# Thunder_F722_Drone_Flight_Controller_202.net
KiCad netlist of a schematic drawn in EasyEDA Pro
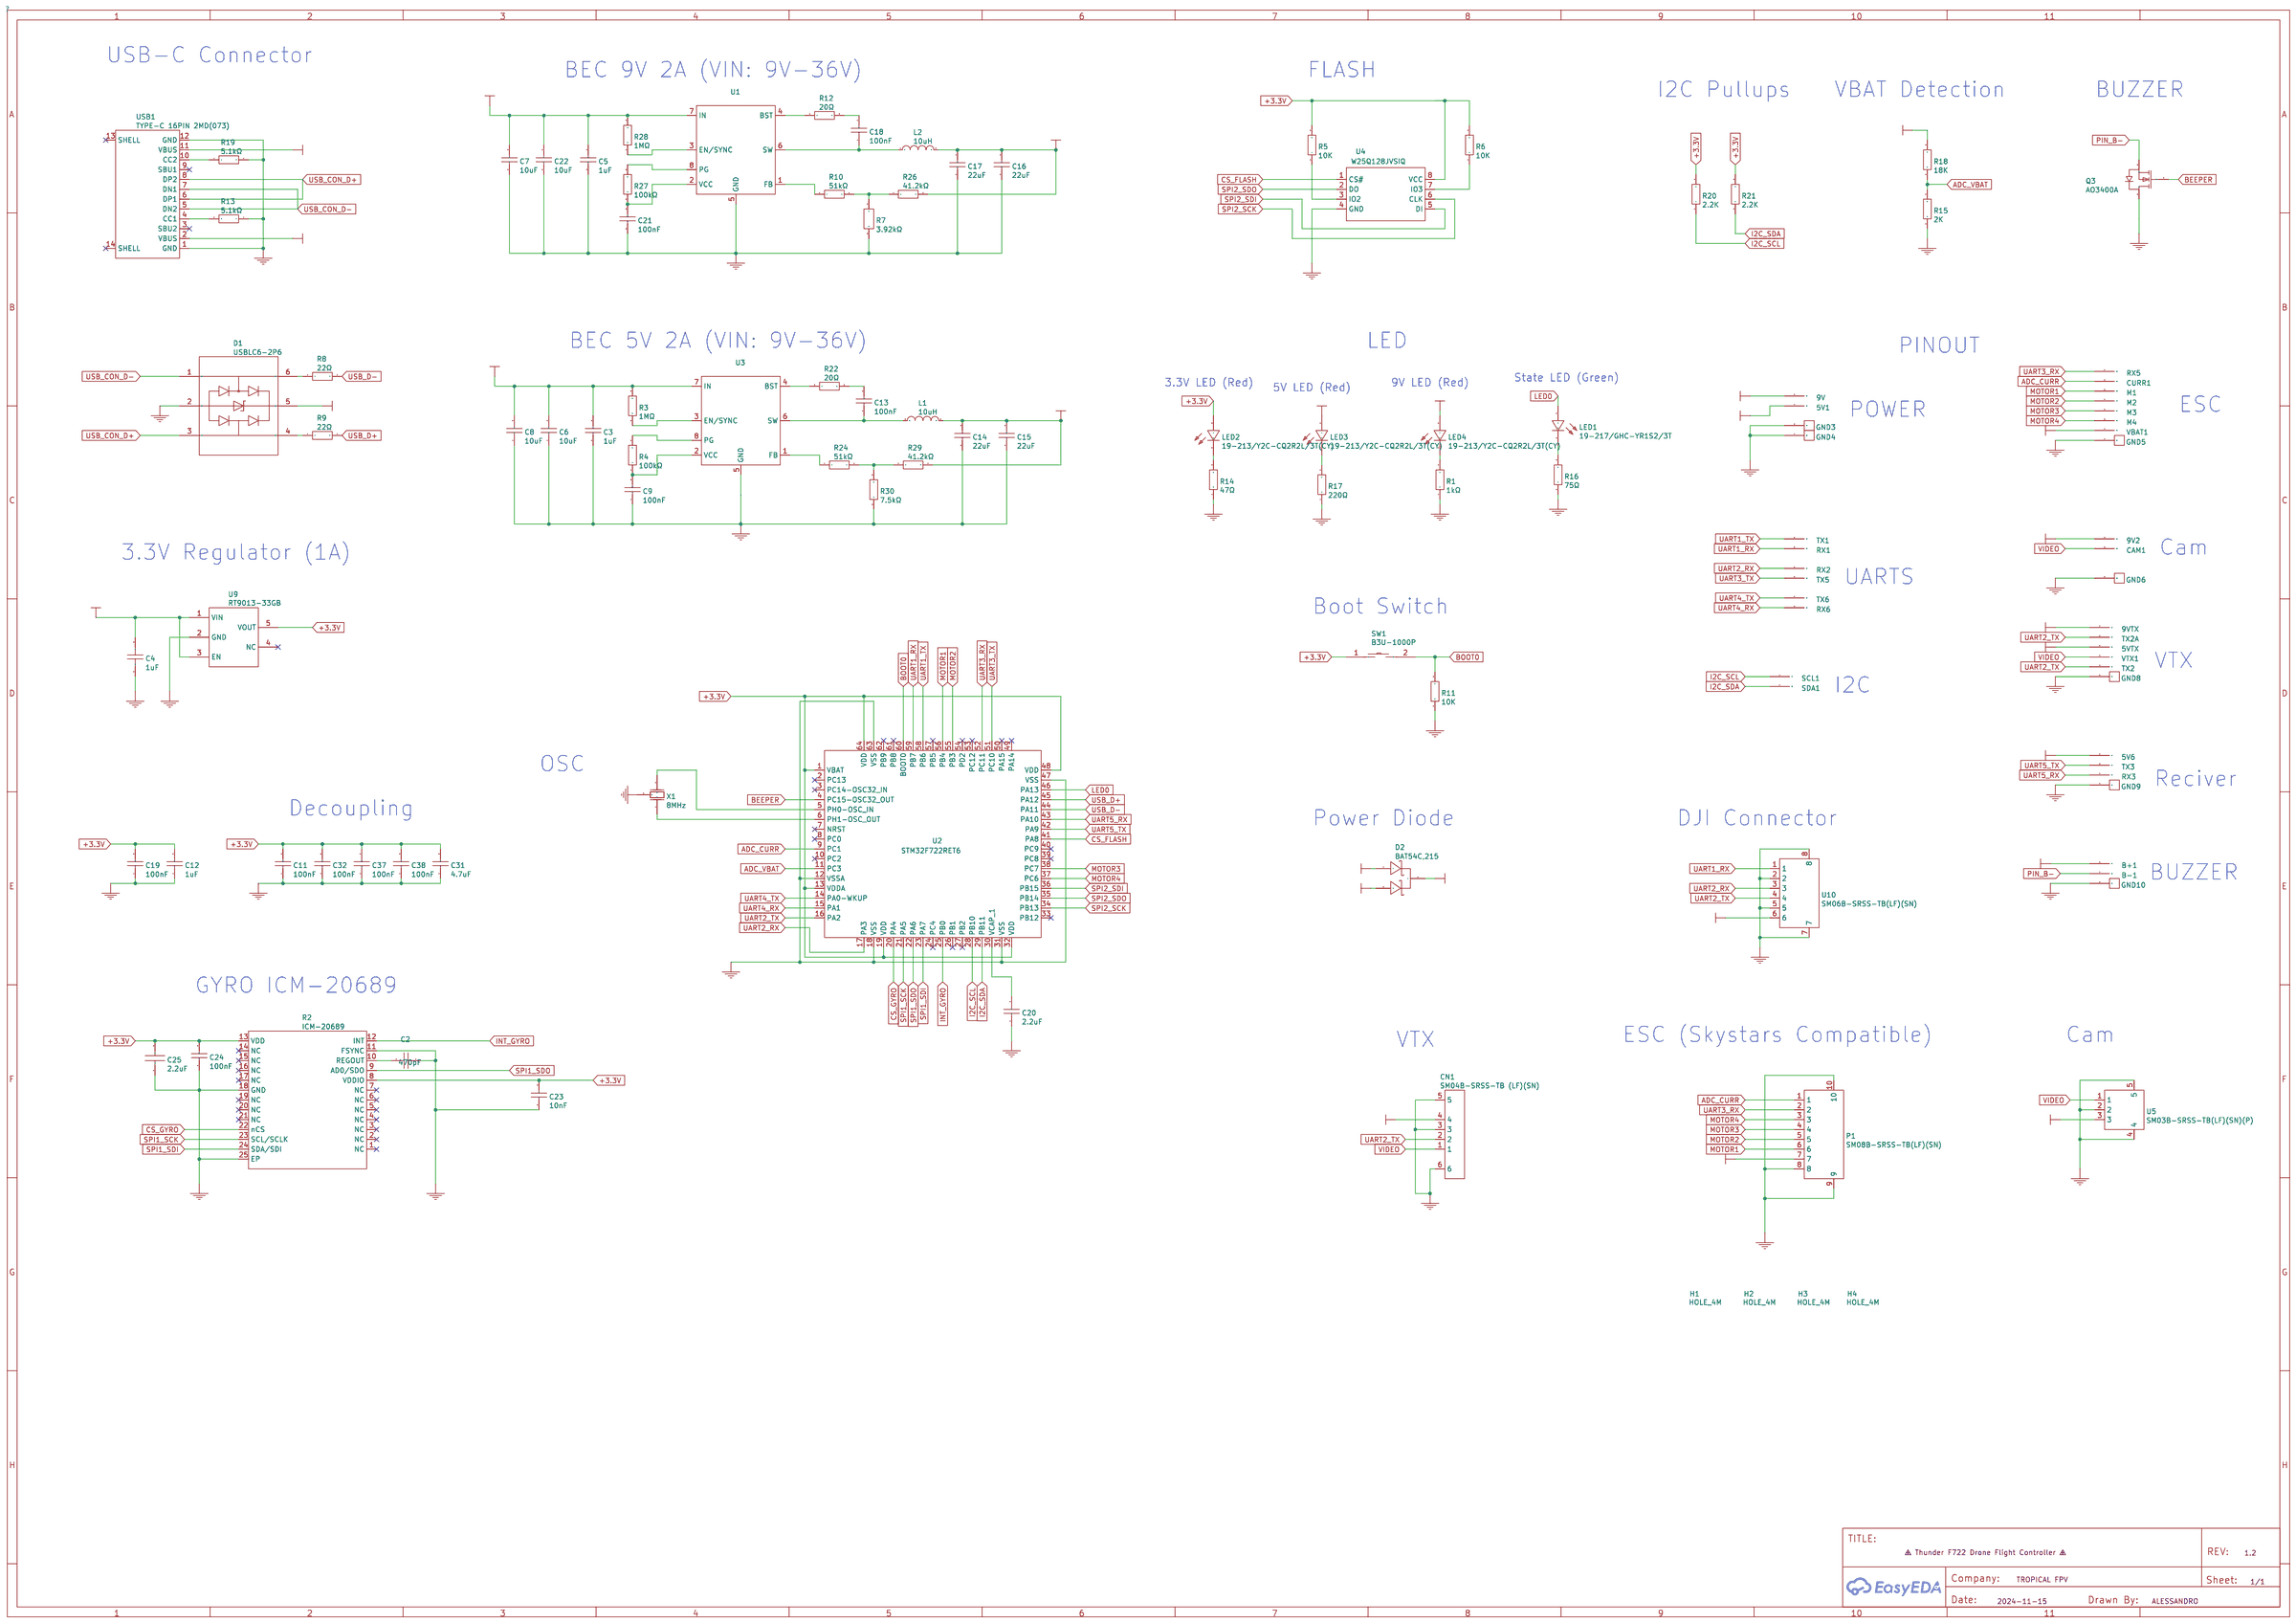
[diagram p0: schematic sheet]

(export (version "E")
  (design (tool "Eeschema 10.0.6"))
  (components
    (comp (ref "5V1")
      (value "ROUND SOLDER PADS WITH HOLE 1.5MM X 2.5MM COPY")
      (footprint "easyedapro:ROUND SOLDER PADS WITH HOLE 1MM X 1.75MM")
      (fields (field (name "Manufacturer Part") "solderpad"))
      (libsource (lib "easyedapro") (part "ROUND SOLDER PADS WITH HOLE 1.5MM X 2.5MM COPY"))
    )
    (comp (ref "5V6")
      (value "ROUND SOLDER PADS WITH HOLE 1.5MM X 2.5MM COPY")
      (footprint "easyedapro:ROUND SOLDER PADS WITH HOLE 1MM X 1.75MM")
      (fields (field (name "Manufacturer Part") "solderpad"))
      (libsource (lib "easyedapro") (part "ROUND SOLDER PADS WITH HOLE 1.5MM X 2.5MM COPY"))
    )
    (comp (ref "5VTX")
      (value "ROUND SOLDER PADS WITH HOLE 1.5MM X 2.5MM COPY")
      (footprint "easyedapro:ROUND SOLDER PADS WITH HOLE 1MM X 1.75MM")
      (fields (field (name "Manufacturer Part") "solderpad"))
      (libsource (lib "easyedapro") (part "ROUND SOLDER PADS WITH HOLE 1.5MM X 2.5MM COPY"))
    )
    (comp (ref "9V")
      (value "ROUND SOLDER PADS WITH HOLE 1.5MM X 2.5MM COPY")
      (footprint "easyedapro:ROUND SOLDER PADS WITH HOLE 1MM X 1.75MM")
      (fields (field (name "Manufacturer Part") "solderpad"))
      (libsource (lib "easyedapro") (part "ROUND SOLDER PADS WITH HOLE 1.5MM X 2.5MM COPY"))
    )
    (comp (ref "9V2")
      (value "ROUND SOLDER PADS WITH HOLE 1.5MM X 2.5MM COPY")
      (footprint "easyedapro:ROUND SOLDER PADS WITH HOLE 1MM X 1.75MM")
      (fields (field (name "Manufacturer Part") "solderpad"))
      (libsource (lib "easyedapro") (part "ROUND SOLDER PADS WITH HOLE 1.5MM X 2.5MM COPY"))
    )
    (comp (ref "9VTX")
      (value "ROUND SOLDER PADS WITH HOLE 1.5MM X 2.5MM COPY")
      (footprint "easyedapro:ROUND SOLDER PADS WITH HOLE 1MM X 1.75MM")
      (fields (field (name "Manufacturer Part") "solderpad"))
      (libsource (lib "easyedapro") (part "ROUND SOLDER PADS WITH HOLE 1.5MM X 2.5MM COPY"))
    )
    (comp (ref "B+1")
      (value "ROUND SOLDER PADS WITH HOLE 1.5MM X 2.5MM COPY")
      (footprint "easyedapro:ROUND SOLDER PADS WITH HOLE 1MM X 1.75MM")
      (fields (field (name "Manufacturer Part") "solderpad"))
      (libsource (lib "easyedapro") (part "ROUND SOLDER PADS WITH HOLE 1.5MM X 2.5MM COPY"))
    )
    (comp (ref "B-1")
      (value "ROUND SOLDER PADS WITH HOLE 1.5MM X 2.5MM COPY")
      (footprint "easyedapro:ROUND SOLDER PADS WITH HOLE 1MM X 1.75MM")
      (fields (field (name "Manufacturer Part") "solderpad"))
      (libsource (lib "easyedapro") (part "ROUND SOLDER PADS WITH HOLE 1.5MM X 2.5MM COPY"))
    )
    (comp (ref "C2")
      (value "470pF")
      (footprint "easyedapro:C0402")
      (fields (field (name "Manufacturer Part") "0402B471K500NT") (field (name "Manufacturer") "FH(风华)"))
      (libsource (lib "easyedapro") (part "470pF"))
    )
    (comp (ref "C3")
      (value "1uF")
      (footprint "easyedapro:C0603")
      (fields (field (name "Manufacturer Part") "CL10A105KB8NNNC") (field (name "Manufacturer") "SAMSUNG"))
      (libsource (lib "easyedapro") (part "1uF"))
    )
    (comp (ref "C4")
      (value "1uF")
      (footprint "easyedapro:C0402")
      (fields (field (name "Manufacturer Part") "CL05A105KA5NQNC") (field (name "Manufacturer") "SAMSUNG"))
      (libsource (lib "") (part "1uF_1"))
    )
    (comp (ref "C5")
      (value "1uF")
      (footprint "easyedapro:C0603")
      (fields (field (name "Manufacturer Part") "CL10A105KB8NNNC") (field (name "Manufacturer") "SAMSUNG"))
      (libsource (lib "easyedapro") (part "1uF"))
    )
    (comp (ref "C6")
      (value "10uF")
      (footprint "easyedapro:C1206")
      (fields (field (name "Manufacturer Part") "CL31A106KBHNNNE") (field (name "Manufacturer") "SAMSUNG"))
      (libsource (lib "easyedapro") (part "10uF"))
    )
    (comp (ref "C7")
      (value "10uF")
      (footprint "easyedapro:C1206")
      (fields (field (name "Manufacturer Part") "CL31A106KBHNNNE") (field (name "Manufacturer") "SAMSUNG"))
      (libsource (lib "easyedapro") (part "10uF"))
    )
    (comp (ref "C8")
      (value "10uF")
      (footprint "easyedapro:C1206")
      (fields (field (name "Manufacturer Part") "CL31A106KBHNNNE") (field (name "Manufacturer") "SAMSUNG"))
      (libsource (lib "easyedapro") (part "10uF"))
    )
    (comp (ref "C9")
      (value "100nF")
      (footprint "easyedapro:C0402")
      (fields (field (name "Manufacturer Part") "CL05B104KO5NNNC") (field (name "Manufacturer") "SAMSUNG"))
      (libsource (lib "easyedapro") (part "100nF"))
    )
    (comp (ref "C11")
      (value "100nF")
      (footprint "easyedapro:C0402")
      (fields (field (name "Manufacturer Part") "CL05B104KO5NNNC") (field (name "Manufacturer") "SAMSUNG"))
      (libsource (lib "easyedapro") (part "100nF"))
    )
    (comp (ref "C12")
      (value "1uF")
      (footprint "easyedapro:C0603")
      (fields (field (name "Manufacturer Part") "CL10A105KB8NNNC") (field (name "Manufacturer") "SAMSUNG"))
      (libsource (lib "easyedapro") (part "1uF"))
    )
    (comp (ref "C13")
      (value "100nF")
      (footprint "easyedapro:C0402")
      (fields (field (name "Manufacturer Part") "CL05B104KO5NNNC") (field (name "Manufacturer") "SAMSUNG"))
      (libsource (lib "easyedapro") (part "100nF"))
    )
    (comp (ref "C14")
      (value "22uF")
      (footprint "easyedapro:C1206")
      (fields
        (field (name "Manufacturer Part") "CL31A226KPHNNNE")
        (field (name "Manufacturer") "SAMSUNG(三星)")
      )
      (libsource (lib "easyedapro") (part "22uF"))
    )
    (comp (ref "C15")
      (value "22uF")
      (footprint "easyedapro:C1206")
      (fields
        (field (name "Manufacturer Part") "CL31A226KPHNNNE")
        (field (name "Manufacturer") "SAMSUNG(三星)")
      )
      (libsource (lib "easyedapro") (part "22uF"))
    )
    (comp (ref "C16")
      (value "22uF")
      (footprint "easyedapro:C1206")
      (fields
        (field (name "Manufacturer Part") "CL31A226KPHNNNE")
        (field (name "Manufacturer") "SAMSUNG(三星)")
      )
      (libsource (lib "easyedapro") (part "22uF"))
    )
    (comp (ref "C17")
      (value "22uF")
      (footprint "easyedapro:C1206")
      (fields
        (field (name "Manufacturer Part") "CL31A226KPHNNNE")
        (field (name "Manufacturer") "SAMSUNG(三星)")
      )
      (libsource (lib "easyedapro") (part "22uF"))
    )
    (comp (ref "C18")
      (value "100nF")
      (footprint "easyedapro:C0402")
      (fields (field (name "Manufacturer Part") "CL05B104KO5NNNC") (field (name "Manufacturer") "SAMSUNG"))
      (libsource (lib "easyedapro") (part "100nF"))
    )
    (comp (ref "C19")
      (value "100nF")
      (footprint "easyedapro:C0402")
      (fields (field (name "Manufacturer Part") "CL05B104KO5NNNC") (field (name "Manufacturer") "SAMSUNG"))
      (libsource (lib "easyedapro") (part "100nF"))
    )
    (comp (ref "C20")
      (value "2.2uF")
      (footprint "easyedapro:C0603")
      (fields (field (name "Manufacturer Part") "CL10A225KO8NNNC") (field (name "Manufacturer") "SAMSUNG"))
      (libsource (lib "") (part "2.2uF_1"))
    )
    (comp (ref "C21")
      (value "100nF")
      (footprint "easyedapro:C0402")
      (fields (field (name "Manufacturer Part") "CL05B104KO5NNNC") (field (name "Manufacturer") "SAMSUNG"))
      (libsource (lib "easyedapro") (part "100nF"))
    )
    (comp (ref "C22")
      (value "10uF")
      (footprint "easyedapro:C1206")
      (fields (field (name "Manufacturer Part") "CL31A106KBHNNNE") (field (name "Manufacturer") "SAMSUNG"))
      (libsource (lib "easyedapro") (part "10uF"))
    )
    (comp (ref "C23")
      (value "10nF")
      (footprint "easyedapro:C0402")
      (fields
        (field (name "Manufacturer Part") "CL05B103KB5NNNC")
        (field (name "Manufacturer") "SAMSUNG(三星)")
      )
      (libsource (lib "easyedapro") (part "10nF"))
    )
    (comp (ref "C24")
      (value "100nF")
      (footprint "easyedapro:C0402")
      (fields (field (name "Manufacturer Part") "CL05B104KO5NNNC") (field (name "Manufacturer") "SAMSUNG"))
      (libsource (lib "easyedapro") (part "100nF"))
    )
    (comp (ref "C25")
      (value "2.2uF")
      (footprint "easyedapro:C0402")
      (fields
        (field (name "Manufacturer Part") "CL05A225MQ5NSNC")
        (field (name "Manufacturer") "SAMSUNG(三星)")
      )
      (libsource (lib "easyedapro") (part "2.2uF"))
    )
    (comp (ref "C31")
      (value "4.7uF")
      (footprint "easyedapro:C0603")
      (fields (field (name "Manufacturer Part") "CL10A475KO8NNNC") (field (name "Manufacturer") "SAMSUNG"))
      (libsource (lib "easyedapro") (part "4.7uF"))
    )
    (comp (ref "C32")
      (value "100nF")
      (footprint "easyedapro:C0402")
      (fields (field (name "Manufacturer Part") "CL05B104KO5NNNC") (field (name "Manufacturer") "SAMSUNG"))
      (libsource (lib "easyedapro") (part "100nF"))
    )
    (comp (ref "C37")
      (value "100nF")
      (footprint "easyedapro:C0402")
      (fields (field (name "Manufacturer Part") "CL05B104KO5NNNC") (field (name "Manufacturer") "SAMSUNG"))
      (libsource (lib "easyedapro") (part "100nF"))
    )
    (comp (ref "C38")
      (value "100nF")
      (footprint "easyedapro:C0402")
      (fields (field (name "Manufacturer Part") "CL05B104KO5NNNC") (field (name "Manufacturer") "SAMSUNG"))
      (libsource (lib "easyedapro") (part "100nF"))
    )
    (comp (ref "CAM1")
      (value "ROUND SOLDER PADS WITH HOLE 1.5MM X 2.5MM COPY")
      (footprint "easyedapro:ROUND SOLDER PADS WITH HOLE 1MM X 1.75MM")
      (fields (field (name "Manufacturer Part") "solderpad"))
      (libsource (lib "easyedapro") (part "ROUND SOLDER PADS WITH HOLE 1.5MM X 2.5MM COPY"))
    )
    (comp (ref "CN1")
      (value "SM04B-SRSS-TB (LF)(SN)")
      (footprint "easyedapro:CONN-SMD_4P-P1.00_SM04B-SRSS-TB-LF-SN")
      (fields (field (name "Manufacturer Part") "SM04B-SRSS-TB(LF)(SN)") (field (name "Manufacturer") "JST"))
      (libsource (lib "easyedapro") (part "SM04B-SRSS-TB (LF)(SN)"))
    )
    (comp (ref "CURR1")
      (value "ROUND SOLDER PADS WITH HOLE 1.5MM X 2.5MM COPY")
      (footprint "easyedapro:ROUND SOLDER PADS WITH HOLE 1MM X 1.75MM")
      (fields (field (name "Manufacturer Part") "solderpad"))
      (libsource (lib "easyedapro") (part "ROUND SOLDER PADS WITH HOLE 1.5MM X 2.5MM COPY"))
    )
    (comp (ref "D1")
      (value "USBLC6-2P6")
      (footprint "easyedapro:SOT-666-6_L1.6-W1.2-P0.50-LS1.6-BR")
      (fields (field (name "Manufacturer") "STMicroelectronics"))
      (libsource (lib "easyedapro") (part "USBLC6-2P6"))
    )
    (comp (ref "D2")
      (value "BAT54C,215")
      (footprint "easyedapro:SOT-23-3_L2.9-W1.6-P1.90-LS2.8-BR")
      (fields (field (name "Manufacturer") "Nexperia(安世)"))
      (libsource (lib "easyedapro") (part "BAT54C,215"))
    )
    (comp (ref "GND3")
      (value "RECTANGLE SOLDER PADS WITH HOLE 1.5MM X 2.5MM")
      (footprint "easyedapro:RECTANGLE SOLDER PADS WITH HOLE 1.25MM X 1.75MM")
      (fields (field (name "Manufacturer Part") "solderpad"))
      (libsource (lib "easyedapro") (part "RECTANGLE SOLDER PADS WITH HOLE 1.5MM X 2.5MM"))
    )
    (comp (ref "GND4")
      (value "RECTANGLE SOLDER PADS WITH HOLE 1.5MM X 2.5MM")
      (footprint "easyedapro:RECTANGLE SOLDER PADS WITH HOLE 1.25MM X 1.75MM")
      (fields (field (name "Manufacturer Part") "solderpad"))
      (libsource (lib "easyedapro") (part "RECTANGLE SOLDER PADS WITH HOLE 1.5MM X 2.5MM"))
    )
    (comp (ref "GND5")
      (value "RECTANGLE SOLDER PADS WITH HOLE 1.5MM X 2.5MM")
      (footprint "easyedapro:RECTANGLE SOLDER PADS WITH HOLE 1.25MM X 1.75MM")
      (fields (field (name "Manufacturer Part") "solderpad"))
      (libsource (lib "easyedapro") (part "RECTANGLE SOLDER PADS WITH HOLE 1.5MM X 2.5MM"))
    )
    (comp (ref "GND6")
      (value "RECTANGLE SOLDER PADS WITH HOLE 1.5MM X 2.5MM")
      (footprint "easyedapro:RECTANGLE SOLDER PADS WITH HOLE 1.25MM X 1.75MM")
      (fields (field (name "Manufacturer Part") "solderpad"))
      (libsource (lib "easyedapro") (part "RECTANGLE SOLDER PADS WITH HOLE 1.5MM X 2.5MM"))
    )
    (comp (ref "GND8")
      (value "RECTANGLE SOLDER PADS WITH HOLE 1.5MM X 2.5MM")
      (footprint "easyedapro:RECTANGLE SOLDER PADS WITH HOLE 1.25MM X 1.75MM")
      (fields (field (name "Manufacturer Part") "solderpad"))
      (libsource (lib "easyedapro") (part "RECTANGLE SOLDER PADS WITH HOLE 1.5MM X 2.5MM"))
    )
    (comp (ref "GND9")
      (value "RECTANGLE SOLDER PADS WITH HOLE 1.5MM X 2.5MM")
      (footprint "easyedapro:RECTANGLE SOLDER PADS WITH HOLE 1.25MM X 1.75MM")
      (fields (field (name "Manufacturer Part") "solderpad"))
      (libsource (lib "easyedapro") (part "RECTANGLE SOLDER PADS WITH HOLE 1.5MM X 2.5MM"))
    )
    (comp (ref "GND10")
      (value "RECTANGLE SOLDER PADS WITH HOLE 1.5MM X 2.5MM")
      (footprint "easyedapro:RECTANGLE SOLDER PADS WITH HOLE 1.25MM X 1.75MM")
      (fields (field (name "Manufacturer Part") "solderpad"))
      (libsource (lib "easyedapro") (part "RECTANGLE SOLDER PADS WITH HOLE 1.5MM X 2.5MM"))
    )
    (comp (ref "H1")
      (value "HOLE_4M")
      (footprint "easyedapro:HOLE_4MM")
      (libsource (lib "easyedapro") (part "HOLE_4M"))
    )
    (comp (ref "H2")
      (value "HOLE_4M")
      (footprint "easyedapro:HOLE_4MM")
      (libsource (lib "easyedapro") (part "HOLE_4M"))
    )
    (comp (ref "H3")
      (value "HOLE_4M")
      (footprint "easyedapro:HOLE_4MM")
      (libsource (lib "easyedapro") (part "HOLE_4M"))
    )
    (comp (ref "H4")
      (value "HOLE_4M")
      (footprint "easyedapro:HOLE_4MM")
      (libsource (lib "easyedapro") (part "HOLE_4M"))
    )
    (comp (ref "L1")
      (value "10uH")
      (footprint "easyedapro:IND-SMD_L4.4-W4.2_PSPMAA0412")
      (fields (field (name "Manufacturer Part") "YSPI0420-100M") (field (name "Manufacturer") "YJYCOIN(益嘉源)"))
      (libsource (lib "easyedapro") (part "10uH"))
    )
    (comp (ref "L2")
      (value "10uH")
      (footprint "easyedapro:IND-SMD_L4.4-W4.2_PSPMAA0412")
      (fields (field (name "Manufacturer Part") "YSPI0420-100M") (field (name "Manufacturer") "YJYCOIN(益嘉源)"))
      (libsource (lib "easyedapro") (part "10uH"))
    )
    (comp (ref "LED1")
      (value "19-217/GHC-YR1S2/3T")
      (footprint "easyedapro:LED0603-R-RD")
      (fields (field (name "Manufacturer") "EVERLIGHT"))
      (libsource (lib "easyedapro") (part "19-217/GHC-YR1S2/3T"))
    )
    (comp (ref "LED2")
      (value "19-213/Y2C-CQ2R2L/3T(CY)")
      (footprint "easyedapro:LED0603-RD-YELLOW")
      (fields (field (name "Manufacturer") "EVERLIGHT(亿光)"))
      (libsource (lib "easyedapro") (part "19-213/Y2C-CQ2R2L/3T(CY)"))
    )
    (comp (ref "LED3")
      (value "19-213/Y2C-CQ2R2L/3T(CY)")
      (footprint "easyedapro:LED0603-RD-YELLOW")
      (fields (field (name "Manufacturer") "EVERLIGHT(亿光)"))
      (libsource (lib "easyedapro") (part "19-213/Y2C-CQ2R2L/3T(CY)"))
    )
    (comp (ref "LED4")
      (value "19-213/Y2C-CQ2R2L/3T(CY)")
      (footprint "easyedapro:LED0603-RD-YELLOW")
      (fields (field (name "Manufacturer") "EVERLIGHT(亿光)"))
      (libsource (lib "easyedapro") (part "19-213/Y2C-CQ2R2L/3T(CY)"))
    )
    (comp (ref "M1")
      (value "ROUND SOLDER PADS WITH HOLE 1.5MM X 2.5MM COPY")
      (footprint "easyedapro:ROUND SOLDER PADS WITH HOLE 1MM X 1.75MM")
      (fields (field (name "Manufacturer Part") "solderpad"))
      (libsource (lib "easyedapro") (part "ROUND SOLDER PADS WITH HOLE 1.5MM X 2.5MM COPY"))
    )
    (comp (ref "M2")
      (value "ROUND SOLDER PADS WITH HOLE 1.5MM X 2.5MM COPY")
      (footprint "easyedapro:ROUND SOLDER PADS WITH HOLE 1MM X 1.75MM")
      (fields (field (name "Manufacturer Part") "solderpad"))
      (libsource (lib "easyedapro") (part "ROUND SOLDER PADS WITH HOLE 1.5MM X 2.5MM COPY"))
    )
    (comp (ref "M3")
      (value "ROUND SOLDER PADS WITH HOLE 1.5MM X 2.5MM COPY")
      (footprint "easyedapro:ROUND SOLDER PADS WITH HOLE 1MM X 1.75MM")
      (fields (field (name "Manufacturer Part") "solderpad"))
      (libsource (lib "easyedapro") (part "ROUND SOLDER PADS WITH HOLE 1.5MM X 2.5MM COPY"))
    )
    (comp (ref "M4")
      (value "ROUND SOLDER PADS WITH HOLE 1.5MM X 2.5MM COPY")
      (footprint "easyedapro:ROUND SOLDER PADS WITH HOLE 1MM X 1.75MM")
      (fields (field (name "Manufacturer Part") "solderpad"))
      (libsource (lib "easyedapro") (part "ROUND SOLDER PADS WITH HOLE 1.5MM X 2.5MM COPY"))
    )
    (comp (ref "P1")
      (value "SM08B-SRSS-TB(LF)(SN)")
      (footprint "easyedapro:CONN-TH_SM08B-SRSS-TB-LF-SN")
      (fields (field (name "Manufacturer") "JST"))
      (libsource (lib "easyedapro") (part "SM08B-SRSS-TB(LF)(SN)"))
    )
    (comp (ref "Q3")
      (value "AO3400A")
      (footprint "easyedapro:SOT-23-3_L2.9-W1.6-P1.90-LS2.8-BR")
      (fields (field (name "Manufacturer") "AOS"))
      (libsource (lib "easyedapro") (part "AO3400A"))
    )
    (comp (ref "R1")
      (value "1kΩ")
      (footprint "easyedapro:R0603")
      (fields
        (field (name "Manufacturer Part") "0603WAF1001T5E")
        (field (name "Manufacturer") "UNI-ROYAL(厚声)")
      )
      (libsource (lib "easyedapro") (part "1kΩ"))
    )
    (comp (ref "R2")
      (value "ICM-20689")
      (footprint "easyedapro:QFN-24_L4.0-W4.0-P0.50-TL-EP2.6")
      (fields (field (name "Manufacturer") "TDK InvenSense(应美盛)"))
      (libsource (lib "easyedapro") (part "ICM-20689"))
    )
    (comp (ref "R3")
      (value "1MΩ")
      (footprint "easyedapro:R0603")
      (fields
        (field (name "Manufacturer Part") "0603WAF1004T5E")
        (field (name "Manufacturer") "UNI-ROYAL(厚声)")
      )
      (libsource (lib "easyedapro") (part "1MΩ"))
    )
    (comp (ref "R4")
      (value "100kΩ")
      (footprint "easyedapro:R0402")
      (fields
        (field (name "Manufacturer Part") "0402WGF1003TCE")
        (field (name "Manufacturer") "UNI-ROYAL(厚声)")
      )
      (libsource (lib "easyedapro") (part "100kΩ"))
    )
    (comp (ref "R5")
      (value "10K")
      (footprint "easyedapro:R0402")
      (fields (field (name "Manufacturer Part") "0402WGF1002TCE") (field (name "Manufacturer") "UniOhm"))
      (libsource (lib "easyedapro") (part "10K"))
    )
    (comp (ref "R6")
      (value "10K")
      (footprint "easyedapro:R0402")
      (fields (field (name "Manufacturer Part") "0402WGF1002TCE") (field (name "Manufacturer") "UniOhm"))
      (libsource (lib "easyedapro") (part "10K"))
    )
    (comp (ref "R7")
      (value "3.92kΩ")
      (footprint "easyedapro:R1206")
      (fields
        (field (name "Manufacturer Part") "1206W4F3921T5E")
        (field (name "Manufacturer") "UNI-ROYAL(厚声)")
      )
      (libsource (lib "easyedapro") (part "3.92kΩ"))
    )
    (comp (ref "R8")
      (value "22Ω")
      (footprint "easyedapro:R0402")
      (fields
        (field (name "Manufacturer Part") "0402WGF220JTCE")
        (field (name "Manufacturer") "UNI-ROYAL(厚声)")
      )
      (libsource (lib "easyedapro") (part "22Ω"))
    )
    (comp (ref "R9")
      (value "22Ω")
      (footprint "easyedapro:R0402")
      (fields
        (field (name "Manufacturer Part") "0402WGF220JTCE")
        (field (name "Manufacturer") "UNI-ROYAL(厚声)")
      )
      (libsource (lib "easyedapro") (part "22Ω"))
    )
    (comp (ref "R10")
      (value "51kΩ")
      (footprint "easyedapro:R0402")
      (fields
        (field (name "Manufacturer Part") "0402WGF5102TCE")
        (field (name "Manufacturer") "UNI-ROYAL(厚声)")
      )
      (libsource (lib "easyedapro") (part "51kΩ"))
    )
    (comp (ref "R11")
      (value "10K")
      (footprint "easyedapro:R0402")
      (fields (field (name "Manufacturer Part") "0402WGF1002TCE") (field (name "Manufacturer") "UniOhm"))
      (libsource (lib "easyedapro") (part "10K"))
    )
    (comp (ref "R12")
      (value "20Ω")
      (footprint "easyedapro:R0603")
      (fields
        (field (name "Manufacturer Part") "0603WAF200JT5E")
        (field (name "Manufacturer") "UNI-ROYAL(厚声)")
      )
      (libsource (lib "easyedapro") (part "20Ω"))
    )
    (comp (ref "R13")
      (value "5.1kΩ")
      (footprint "easyedapro:R0402")
      (fields
        (field (name "Manufacturer Part") "0402WGF5101TCE")
        (field (name "Manufacturer") "UNI-ROYAL(厚声)")
      )
      (libsource (lib "easyedapro") (part "5.1kΩ"))
    )
    (comp (ref "R14")
      (value "47Ω")
      (footprint "easyedapro:R0402")
      (fields (field (name "Manufacturer Part") "0402WGF470JTCE") (field (name "Manufacturer") "UniOhm"))
      (libsource (lib "easyedapro") (part "47Ω"))
    )
    (comp (ref "R15")
      (value "2K")
      (footprint "easyedapro:R0402")
      (fields (field (name "Manufacturer Part") "0402WGF2001TCE") (field (name "Manufacturer") "UniOhm"))
      (libsource (lib "easyedapro") (part "2K"))
    )
    (comp (ref "R16")
      (value "75Ω")
      (footprint "easyedapro:R0603")
      (fields (field (name "Manufacturer Part") "0603WAF750JT5E") (field (name "Manufacturer") "UniOhm"))
      (libsource (lib "easyedapro") (part "75Ω"))
    )
    (comp (ref "R17")
      (value "220Ω")
      (footprint "easyedapro:R0402")
      (fields (field (name "Manufacturer Part") "0402WGF2200TCE") (field (name "Manufacturer") "UniOhm"))
      (libsource (lib "easyedapro") (part "220Ω"))
    )
    (comp (ref "R18")
      (value "18K")
      (footprint "easyedapro:R0402")
      (fields (field (name "Manufacturer Part") "0402WGF1802TCE") (field (name "Manufacturer") "UniOhm"))
      (libsource (lib "easyedapro") (part "18K"))
    )
    (comp (ref "R19")
      (value "5.1kΩ")
      (footprint "easyedapro:R0402")
      (fields
        (field (name "Manufacturer Part") "0402WGF5101TCE")
        (field (name "Manufacturer") "UNI-ROYAL(厚声)")
      )
      (libsource (lib "easyedapro") (part "5.1kΩ"))
    )
    (comp (ref "R20")
      (value "2.2K")
      (footprint "easyedapro:R0402")
      (fields (field (name "Manufacturer Part") "0402WGF2201TCE") (field (name "Manufacturer") "UniOhm"))
      (libsource (lib "easyedapro") (part "2.2K"))
    )
    (comp (ref "R21")
      (value "2.2K")
      (footprint "easyedapro:R0402")
      (fields (field (name "Manufacturer Part") "0402WGF2201TCE") (field (name "Manufacturer") "UniOhm"))
      (libsource (lib "easyedapro") (part "2.2K"))
    )
    (comp (ref "R22")
      (value "20Ω")
      (footprint "easyedapro:R0603")
      (fields
        (field (name "Manufacturer Part") "0603WAF200JT5E")
        (field (name "Manufacturer") "UNI-ROYAL(厚声)")
      )
      (libsource (lib "easyedapro") (part "20Ω"))
    )
    (comp (ref "R24")
      (value "51kΩ")
      (footprint "easyedapro:R0402")
      (fields
        (field (name "Manufacturer Part") "0402WGF5102TCE")
        (field (name "Manufacturer") "UNI-ROYAL(厚声)")
      )
      (libsource (lib "easyedapro") (part "51kΩ"))
    )
    (comp (ref "R26")
      (value "41.2kΩ")
      (footprint "easyedapro:R1206")
      (fields (field (name "Manufacturer Part") "RS-06K4122FT") (field (name "Manufacturer") "FH(风华)"))
      (libsource (lib "easyedapro") (part "41.2kΩ"))
    )
    (comp (ref "R27")
      (value "100kΩ")
      (footprint "easyedapro:R0402")
      (fields
        (field (name "Manufacturer Part") "0402WGF1003TCE")
        (field (name "Manufacturer") "UNI-ROYAL(厚声)")
      )
      (libsource (lib "easyedapro") (part "100kΩ"))
    )
    (comp (ref "R28")
      (value "1MΩ")
      (footprint "easyedapro:R0603")
      (fields
        (field (name "Manufacturer Part") "0603WAF1004T5E")
        (field (name "Manufacturer") "UNI-ROYAL(厚声)")
      )
      (libsource (lib "easyedapro") (part "1MΩ"))
    )
    (comp (ref "R29")
      (value "41.2kΩ")
      (footprint "easyedapro:R1206")
      (fields (field (name "Manufacturer Part") "RS-06K4122FT") (field (name "Manufacturer") "FH(风华)"))
      (libsource (lib "easyedapro") (part "41.2kΩ"))
    )
    (comp (ref "R30")
      (value "7.5kΩ")
      (footprint "easyedapro:R0402")
      (fields
        (field (name "Manufacturer Part") "0402WGF7501TCE")
        (field (name "Manufacturer") "UNI-ROYAL(厚声)")
      )
      (libsource (lib "easyedapro") (part "7.5kΩ"))
    )
    (comp (ref "RX1")
      (value "ROUND SOLDER PADS WITH HOLE 1.5MM X 2.5MM COPY")
      (footprint "easyedapro:ROUND SOLDER PADS WITH HOLE 1MM X 1.75MM")
      (fields (field (name "Manufacturer Part") "solderpad"))
      (libsource (lib "easyedapro") (part "ROUND SOLDER PADS WITH HOLE 1.5MM X 2.5MM COPY"))
    )
    (comp (ref "RX2")
      (value "ROUND SOLDER PADS WITH HOLE 1.5MM X 2.5MM COPY")
      (footprint "easyedapro:ROUND SOLDER PADS WITH HOLE 1MM X 1.75MM")
      (fields (field (name "Manufacturer Part") "solderpad"))
      (libsource (lib "easyedapro") (part "ROUND SOLDER PADS WITH HOLE 1.5MM X 2.5MM COPY"))
    )
    (comp (ref "RX3")
      (value "ROUND SOLDER PADS WITH HOLE 1.5MM X 2.5MM COPY")
      (footprint "easyedapro:ROUND SOLDER PADS WITH HOLE 1MM X 1.75MM")
      (fields (field (name "Manufacturer Part") "solderpad"))
      (libsource (lib "easyedapro") (part "ROUND SOLDER PADS WITH HOLE 1.5MM X 2.5MM COPY"))
    )
    (comp (ref "RX5")
      (value "ROUND SOLDER PADS WITH HOLE 1.5MM X 2.5MM COPY")
      (footprint "easyedapro:ROUND SOLDER PADS WITH HOLE 1MM X 1.75MM")
      (fields (field (name "Manufacturer Part") "solderpad"))
      (libsource (lib "easyedapro") (part "ROUND SOLDER PADS WITH HOLE 1.5MM X 2.5MM COPY"))
    )
    (comp (ref "RX6")
      (value "ROUND SOLDER PADS WITH HOLE 1.5MM X 2.5MM COPY")
      (footprint "easyedapro:ROUND SOLDER PADS WITH HOLE 1MM X 1.75MM")
      (fields (field (name "Manufacturer Part") "solderpad"))
      (libsource (lib "easyedapro") (part "ROUND SOLDER PADS WITH HOLE 1.5MM X 2.5MM COPY"))
    )
    (comp (ref "SCL1")
      (value "ROUND SOLDER PADS WITH HOLE 1.5MM X 2.5MM COPY")
      (footprint "easyedapro:ROUND SOLDER PADS WITH HOLE 1MM X 1.75MM")
      (fields (field (name "Manufacturer Part") "solderpad"))
      (libsource (lib "easyedapro") (part "ROUND SOLDER PADS WITH HOLE 1.5MM X 2.5MM COPY"))
    )
    (comp (ref "SDA1")
      (value "ROUND SOLDER PADS WITH HOLE 1.5MM X 2.5MM COPY")
      (footprint "easyedapro:ROUND SOLDER PADS WITH HOLE 1MM X 1.75MM")
      (fields (field (name "Manufacturer Part") "solderpad"))
      (libsource (lib "easyedapro") (part "ROUND SOLDER PADS WITH HOLE 1.5MM X 2.5MM COPY"))
    )
    (comp (ref "SW1")
      (value "B3U-1000P")
      (footprint "easyedapro:KEY-SMD_B3U-1000PM")
      (fields (field (name "Manufacturer") "OMRON(欧姆龙)"))
      (libsource (lib "easyedapro") (part "B3U-1000P"))
    )
    (comp (ref "TX1")
      (value "ROUND SOLDER PADS WITH HOLE 1.5MM X 2.5MM COPY")
      (footprint "easyedapro:ROUND SOLDER PADS WITH HOLE 1MM X 1.75MM")
      (fields (field (name "Manufacturer Part") "solderpad"))
      (libsource (lib "easyedapro") (part "ROUND SOLDER PADS WITH HOLE 1.5MM X 2.5MM COPY"))
    )
    (comp (ref "TX2")
      (value "ROUND SOLDER PADS WITH HOLE 1.5MM X 2.5MM COPY")
      (footprint "easyedapro:ROUND SOLDER PADS WITH HOLE 1MM X 1.75MM")
      (fields (field (name "Manufacturer Part") "solderpad"))
      (libsource (lib "easyedapro") (part "ROUND SOLDER PADS WITH HOLE 1.5MM X 2.5MM COPY"))
    )
    (comp (ref "TX2A")
      (value "ROUND SOLDER PADS WITH HOLE 1.5MM X 2.5MM COPY")
      (footprint "easyedapro:ROUND SOLDER PADS WITH HOLE 1MM X 1.75MM")
      (fields (field (name "Manufacturer Part") "solderpad"))
      (libsource (lib "easyedapro") (part "ROUND SOLDER PADS WITH HOLE 1.5MM X 2.5MM COPY"))
    )
    (comp (ref "TX3")
      (value "ROUND SOLDER PADS WITH HOLE 1.5MM X 2.5MM COPY")
      (footprint "easyedapro:ROUND SOLDER PADS WITH HOLE 1MM X 1.75MM")
      (fields (field (name "Manufacturer Part") "solderpad"))
      (libsource (lib "easyedapro") (part "ROUND SOLDER PADS WITH HOLE 1.5MM X 2.5MM COPY"))
    )
    (comp (ref "TX5")
      (value "ROUND SOLDER PADS WITH HOLE 1.5MM X 2.5MM COPY")
      (footprint "easyedapro:ROUND SOLDER PADS WITH HOLE 1MM X 1.75MM")
      (fields (field (name "Manufacturer Part") "solderpad"))
      (libsource (lib "easyedapro") (part "ROUND SOLDER PADS WITH HOLE 1.5MM X 2.5MM COPY"))
    )
    (comp (ref "TX6")
      (value "ROUND SOLDER PADS WITH HOLE 1.5MM X 2.5MM COPY")
      (footprint "easyedapro:ROUND SOLDER PADS WITH HOLE 1MM X 1.75MM")
      (fields (field (name "Manufacturer Part") "solderpad"))
      (libsource (lib "easyedapro") (part "ROUND SOLDER PADS WITH HOLE 1.5MM X 2.5MM COPY"))
    )
    (comp (ref "U1")
      (value "NO")
      (footprint "easyedapro:QFN-8_L3.0-W3.0-P0.65-BL")
      (fields (field (name "Manufacturer Part") "MP9943GQ-Z"))
      (libsource (lib "easyedapro") (part "NO"))
    )
    (comp (ref "U2")
      (value "STM32F722RET6")
      (footprint "easyedapro:LQFP-64_L10.0-W10.0-P0.50-LS12.0-BL")
      (fields (field (name "Manufacturer") "STMicroelectronics"))
      (libsource (lib "easyedapro") (part "STM32F722RET6"))
    )
    (comp (ref "U3")
      (value "NO")
      (footprint "easyedapro:QFN-8_L3.0-W3.0-P0.65-BL")
      (fields (field (name "Manufacturer Part") "MP9943GQ-Z"))
      (libsource (lib "easyedapro") (part "NO"))
    )
    (comp (ref "U4")
      (value "W25Q128JVSIQ")
      (footprint "easyedapro:SOIC-8_L5.3-W5.3-P1.27-LS8.0-BL")
      (fields (field (name "Manufacturer") "WINBOND"))
      (libsource (lib "easyedapro") (part "W25Q128JVSIQ"))
    )
    (comp (ref "U5")
      (value "SM03B-SRSS-TB(LF)(SN)(P)")
      (footprint "easyedapro:CONN-SMD_SM03B-SRSS-TB-LF-SN-P")
      (fields (field (name "Manufacturer Part") "SM03B-SRSS-TB(LF)(SN)") (field (name "Manufacturer") "JST"))
      (libsource (lib "easyedapro") (part "SM03B-SRSS-TB(LF)(SN)(P)"))
    )
    (comp (ref "U9")
      (value "RT9013-33GB")
      (footprint "easyedapro:SOT-23-5_L3.0-W1.7-P0.95-LS2.8-BR")
      (fields (field (name "Manufacturer") "RICHTEK"))
      (libsource (lib "easyedapro") (part "RT9013-33GB"))
    )
    (comp (ref "U10")
      (value "SM06B-SRSS-TB(LF)(SN)")
      (footprint "easyedapro:CONN-SMD_SM06B-SRSS-TB(LF)(SN)")
      (fields (field (name "Manufacturer") "JST Sales America"))
      (libsource (lib "easyedapro") (part "SM06B-SRSS-TB(LF)(SN)"))
    )
    (comp (ref "USB1")
      (value "TYPE-C 16PIN 2MD(073)")
      (footprint "easyedapro:USB-C-SMD_TYPE-C-6PIN-2MD-073")
      (fields (field (name "Manufacturer") "SHOU HAN(首韩)"))
      (libsource (lib "easyedapro") (part "TYPE-C 16PIN 2MD(073)"))
    )
    (comp (ref "VBAT1")
      (value "ROUND SOLDER PADS WITH HOLE 1.5MM X 2.5MM COPY")
      (footprint "easyedapro:ROUND SOLDER PADS WITH HOLE 1MM X 1.75MM")
      (fields (field (name "Manufacturer Part") "solderpad"))
      (libsource (lib "easyedapro") (part "ROUND SOLDER PADS WITH HOLE 1.5MM X 2.5MM COPY"))
    )
    (comp (ref "VTX1")
      (value "ROUND SOLDER PADS WITH HOLE 1.5MM X 2.5MM COPY")
      (footprint "easyedapro:ROUND SOLDER PADS WITH HOLE 1MM X 1.75MM")
      (fields (field (name "Manufacturer Part") "solderpad"))
      (libsource (lib "easyedapro") (part "ROUND SOLDER PADS WITH HOLE 1.5MM X 2.5MM COPY"))
    )
    (comp (ref "X1")
      (value "8MHz")
      (footprint "easyedapro:OSC-SMD_3P-L3.2-W1.3-P1.20-L")
      (fields
        (field (name "Manufacturer Part") "CSTNE8M00G550000R0")
        (field (name "Manufacturer") "muRata(村田)")
      )
      (libsource (lib "easyedapro") (part "8MHz"))
    )
  )
  (nets
    (net (code "1") (name "+3.3V") (class "Default")
      (node (ref "C11") (pin "2") (pinfunction "2_2") (pintype "input"))
      (node (ref "C12") (pin "2") (pinfunction "2_2") (pintype "input"))
      (node (ref "C19") (pin "2") (pinfunction "2_2") (pintype "input"))
      (node (ref "C23") (pin "2") (pinfunction "2_2") (pintype "input"))
      (node (ref "C24") (pin "2") (pinfunction "2_2") (pintype "input"))
      (node (ref "C25") (pin "2") (pinfunction "2_2") (pintype "unspecified"))
      (node (ref "C31") (pin "2") (pinfunction "2_2") (pintype "input"))
      (node (ref "C32") (pin "2") (pinfunction "2_2") (pintype "input"))
      (node (ref "C37") (pin "2") (pinfunction "2_2") (pintype "input"))
      (node (ref "C38") (pin "2") (pinfunction "2_2") (pintype "input"))
      (node (ref "LED2") (pin "2") (pinfunction "A_2") (pintype "input"))
      (node (ref "R2") (pin "13") (pinfunction "VDD_13") (pintype "unspecified"))
      (node (ref "R2") (pin "8") (pinfunction "VDDIO_8") (pintype "unspecified"))
      (node (ref "R20") (pin "2") (pinfunction "2_2") (pintype "input"))
      (node (ref "R21") (pin "2") (pinfunction "2_2") (pintype "input"))
      (node (ref "R5") (pin "2") (pinfunction "2_2") (pintype "input"))
      (node (ref "R6") (pin "2") (pinfunction "2_2") (pintype "input"))
      (node (ref "SW1") (pin "1") (pinfunction "1_1") (pintype "unspecified"))
      (node (ref "U2") (pin "1") (pinfunction "VBAT_1") (pintype "unspecified"))
      (node (ref "U2") (pin "13") (pinfunction "VDDA_13") (pintype "unspecified"))
      (node (ref "U2") (pin "19") (pinfunction "VDD_19") (pintype "unspecified"))
      (node (ref "U2") (pin "32") (pinfunction "VDD_32") (pintype "unspecified"))
      (node (ref "U2") (pin "48") (pinfunction "VDD_48") (pintype "unspecified"))
      (node (ref "U2") (pin "64") (pinfunction "VDD_64") (pintype "unspecified"))
      (node (ref "U4") (pin "8") (pinfunction "VCC_8") (pintype "unspecified"))
      (node (ref "U9") (pin "5") (pinfunction "VOUT_5") (pintype "unspecified"))
    )
    (net (code "2") (name "+5V") (class "Default")
      (node (ref "5V1") (pin "1") (pinfunction "pad_1") (pintype "unspecified"))
      (node (ref "5V6") (pin "1") (pinfunction "pad_1") (pintype "unspecified"))
      (node (ref "5VTX") (pin "1") (pinfunction "pad_1") (pintype "unspecified"))
      (node (ref "B+1") (pin "1") (pinfunction "pad_1") (pintype "unspecified"))
      (node (ref "C4") (pin "2") (pinfunction "2_2") (pintype "unspecified"))
      (node (ref "CN1") (pin "4") (pinfunction "4_4") (pintype "unspecified"))
      (node (ref "D2") (pin "3") (pinfunction "K_3") (pintype "unspecified"))
      (node (ref "LED3") (pin "2") (pinfunction "A_2") (pintype "input"))
      (node (ref "U9") (pin "1") (pinfunction "VIN_1") (pintype "unspecified"))
      (node (ref "U9") (pin "3") (pinfunction "EN_3") (pintype "unspecified"))
    )
    (net (code "3") (name "+5VBAT") (class "Default")
      (node (ref "C14") (pin "2") (pinfunction "2_2") (pintype "input"))
      (node (ref "C15") (pin "2") (pinfunction "2_2") (pintype "input"))
      (node (ref "D2") (pin "1") (pinfunction "A_1") (pintype "unspecified"))
      (node (ref "L1") (pin "2") (pinfunction "2_2") (pintype "unspecified"))
      (node (ref "R29") (pin "2") (pinfunction "2_2") (pintype "unspecified"))
    )
    (net (code "4") (name "+5VBUS") (class "Default")
      (node (ref "D1") (pin "5") (pinfunction "VBUS_5") (pintype "input"))
      (node (ref "D2") (pin "2") (pinfunction "A_2") (pintype "unspecified"))
      (node (ref "USB1") (pin "11") (pinfunction "VBUS_11") (pintype "unspecified"))
      (node (ref "USB1") (pin "2") (pinfunction "VBUS_2") (pintype "unspecified"))
    )
    (net (code "5") (name "+9V") (class "Default")
      (node (ref "9V") (pin "1") (pinfunction "pad_1") (pintype "unspecified"))
      (node (ref "9V2") (pin "1") (pinfunction "pad_1") (pintype "unspecified"))
      (node (ref "9VTX") (pin "1") (pinfunction "pad_1") (pintype "unspecified"))
      (node (ref "C16") (pin "2") (pinfunction "2_2") (pintype "input"))
      (node (ref "C17") (pin "2") (pinfunction "2_2") (pintype "input"))
      (node (ref "L2") (pin "2") (pinfunction "2_2") (pintype "unspecified"))
      (node (ref "LED4") (pin "2") (pinfunction "A_2") (pintype "input"))
      (node (ref "R26") (pin "2") (pinfunction "2_2") (pintype "unspecified"))
      (node (ref "U10") (pin "6") (pinfunction "6_6") (pintype "unspecified"))
      (node (ref "U5") (pin "3") (pinfunction "3_3") (pintype "unspecified"))
    )
    (net (code "6") (name "+VLIPO") (class "Default")
      (node (ref "C22") (pin "2") (pinfunction "2_2") (pintype "input"))
      (node (ref "C3") (pin "2") (pinfunction "2_2") (pintype "input"))
      (node (ref "C5") (pin "2") (pinfunction "2_2") (pintype "input"))
      (node (ref "C6") (pin "2") (pinfunction "2_2") (pintype "input"))
      (node (ref "C7") (pin "2") (pinfunction "2_2") (pintype "input"))
      (node (ref "C8") (pin "2") (pinfunction "2_2") (pintype "input"))
      (node (ref "P1") (pin "7") (pinfunction "7_7") (pintype "unspecified"))
      (node (ref "R18") (pin "2") (pinfunction "2_2") (pintype "input"))
      (node (ref "R28") (pin "2") (pinfunction "2_2") (pintype "input"))
      (node (ref "R3") (pin "2") (pinfunction "2_2") (pintype "input"))
      (node (ref "U1") (pin "7") (pinfunction "IN_7") (pintype "unspecified"))
      (node (ref "U3") (pin "7") (pinfunction "IN_7") (pintype "unspecified"))
      (node (ref "VBAT1") (pin "1") (pinfunction "pad_1") (pintype "unspecified"))
    )
    (net (code "7") (name "ADC_CURR") (class "Default")
      (node (ref "CURR1") (pin "1") (pinfunction "pad_1") (pintype "unspecified"))
      (node (ref "P1") (pin "1") (pinfunction "1_1") (pintype "unspecified"))
      (node (ref "U2") (pin "9") (pinfunction "PC1_9") (pintype "unspecified"))
    )
    (net (code "8") (name "ADC_VBAT") (class "Default")
      (node (ref "R15") (pin "2") (pinfunction "2_2") (pintype "input"))
      (node (ref "R18") (pin "1") (pinfunction "1_1") (pintype "input"))
      (node (ref "U2") (pin "11") (pinfunction "PC3_11") (pintype "unspecified"))
    )
    (net (code "9") (name "BEEPER") (class "Default")
      (node (ref "Q3") (pin "1") (pinfunction "G_1") (pintype "unspecified"))
      (node (ref "U2") (pin "4") (pinfunction "PC15-OSC32_OUT_4") (pintype "unspecified"))
    )
    (net (code "10") (name "BOOT0") (class "Default")
      (node (ref "R11") (pin "2") (pinfunction "2_2") (pintype "input"))
      (node (ref "SW1") (pin "2") (pinfunction "2_2") (pintype "unspecified"))
      (node (ref "U2") (pin "60") (pinfunction "BOOT0_60") (pintype "unspecified"))
    )
    (net (code "11") (name "CS_FLASH") (class "Default")
      (node (ref "U2") (pin "41") (pinfunction "PA8_41") (pintype "unspecified"))
      (node (ref "U4") (pin "1") (pinfunction "CS#_1") (pintype "unspecified"))
    )
    (net (code "12") (name "CS_GYRO") (class "Default")
      (node (ref "R2") (pin "22") (pinfunction "nCS_22") (pintype "unspecified"))
      (node (ref "U2") (pin "20") (pinfunction "PA4_20") (pintype "unspecified"))
    )
    (net (code "13") (name "GND") (class "Default")
      (node (ref "C11") (pin "1") (pinfunction "1_1") (pintype "input"))
      (node (ref "C12") (pin "1") (pinfunction "1_1") (pintype "input"))
      (node (ref "C14") (pin "1") (pinfunction "1_1") (pintype "input"))
      (node (ref "C15") (pin "1") (pinfunction "1_1") (pintype "input"))
      (node (ref "C16") (pin "1") (pinfunction "1_1") (pintype "input"))
      (node (ref "C17") (pin "1") (pinfunction "1_1") (pintype "input"))
      (node (ref "C19") (pin "1") (pinfunction "1_1") (pintype "input"))
      (node (ref "C2") (pin "1") (pinfunction "1_1") (pintype "input"))
      (node (ref "C20") (pin "1") (pinfunction "1_1") (pintype "input"))
      (node (ref "C21") (pin "1") (pinfunction "1_1") (pintype "input"))
      (node (ref "C22") (pin "1") (pinfunction "1_1") (pintype "input"))
      (node (ref "C23") (pin "1") (pinfunction "1_1") (pintype "input"))
      (node (ref "C24") (pin "1") (pinfunction "1_1") (pintype "input"))
      (node (ref "C25") (pin "1") (pinfunction "1_1") (pintype "unspecified"))
      (node (ref "C3") (pin "1") (pinfunction "1_1") (pintype "input"))
      (node (ref "C31") (pin "1") (pinfunction "1_1") (pintype "input"))
      (node (ref "C32") (pin "1") (pinfunction "1_1") (pintype "input"))
      (node (ref "C37") (pin "1") (pinfunction "1_1") (pintype "input"))
      (node (ref "C38") (pin "1") (pinfunction "1_1") (pintype "input"))
      (node (ref "C4") (pin "1") (pinfunction "1_1") (pintype "unspecified"))
      (node (ref "C5") (pin "1") (pinfunction "1_1") (pintype "input"))
      (node (ref "C6") (pin "1") (pinfunction "1_1") (pintype "input"))
      (node (ref "C7") (pin "1") (pinfunction "1_1") (pintype "input"))
      (node (ref "C8") (pin "1") (pinfunction "1_1") (pintype "input"))
      (node (ref "C9") (pin "1") (pinfunction "1_1") (pintype "input"))
      (node (ref "CN1") (pin "3") (pinfunction "3_3") (pintype "unspecified"))
      (node (ref "CN1") (pin "5") (pinfunction "5_5") (pintype "unspecified"))
      (node (ref "CN1") (pin "6") (pinfunction "6_6") (pintype "unspecified"))
      (node (ref "D1") (pin "2") (pinfunction "GND_2") (pintype "input"))
      (node (ref "GND10") (pin "1") (pinfunction "pad_1") (pintype "unspecified"))
      (node (ref "GND3") (pin "1") (pinfunction "pad_1") (pintype "unspecified"))
      (node (ref "GND4") (pin "1") (pinfunction "pad_1") (pintype "unspecified"))
      (node (ref "GND5") (pin "1") (pinfunction "pad_1") (pintype "unspecified"))
      (node (ref "GND6") (pin "1") (pinfunction "pad_1") (pintype "unspecified"))
      (node (ref "GND8") (pin "1") (pinfunction "pad_1") (pintype "unspecified"))
      (node (ref "GND9") (pin "1") (pinfunction "pad_1") (pintype "unspecified"))
      (node (ref "P1") (pin "10") (pinfunction "10_10") (pintype "unspecified"))
      (node (ref "P1") (pin "8") (pinfunction "8_8") (pintype "unspecified"))
      (node (ref "P1") (pin "9") (pinfunction "9_9") (pintype "unspecified"))
      (node (ref "Q3") (pin "3") (pinfunction "D_3") (pintype "unspecified"))
      (node (ref "R1") (pin "1") (pinfunction "1_1") (pintype "input"))
      (node (ref "R11") (pin "1") (pinfunction "1_1") (pintype "input"))
      (node (ref "R13") (pin "1") (pinfunction "1_1") (pintype "input"))
      (node (ref "R14") (pin "1") (pinfunction "1_1") (pintype "input"))
      (node (ref "R15") (pin "1") (pinfunction "1_1") (pintype "input"))
      (node (ref "R16") (pin "1") (pinfunction "1_1") (pintype "input"))
      (node (ref "R17") (pin "1") (pinfunction "1_1") (pintype "input"))
      (node (ref "R19") (pin "2") (pinfunction "2_2") (pintype "input"))
      (node (ref "R2") (pin "11") (pinfunction "FSYNC_11") (pintype "unspecified"))
      (node (ref "R2") (pin "18") (pinfunction "GND_18") (pintype "unspecified"))
      (node (ref "R2") (pin "25") (pinfunction "EP_25") (pintype "unspecified"))
      (node (ref "R30") (pin "1") (pinfunction "1_1") (pintype "input"))
      (node (ref "R7") (pin "2") (pinfunction "2_2") (pintype "unspecified"))
      (node (ref "U1") (pin "5") (pinfunction "GND_5") (pintype "unspecified"))
      (node (ref "U10") (pin "2") (pinfunction "2_2") (pintype "unspecified"))
      (node (ref "U10") (pin "5") (pinfunction "5_5") (pintype "unspecified"))
      (node (ref "U10") (pin "7") (pinfunction "7_7") (pintype "unspecified"))
      (node (ref "U10") (pin "8") (pinfunction "8_8") (pintype "unspecified"))
      (node (ref "U2") (pin "12") (pinfunction "VSSA_12") (pintype "unspecified"))
      (node (ref "U2") (pin "18") (pinfunction "VSS_18") (pintype "unspecified"))
      (node (ref "U2") (pin "31") (pinfunction "VSS_31") (pintype "unspecified"))
      (node (ref "U2") (pin "47") (pinfunction "VSS_47") (pintype "unspecified"))
      (node (ref "U2") (pin "63") (pinfunction "VSS_63") (pintype "unspecified"))
      (node (ref "U3") (pin "5") (pinfunction "GND_5") (pintype "unspecified"))
      (node (ref "U4") (pin "4") (pinfunction "GND_4") (pintype "unspecified"))
      (node (ref "U5") (pin "2") (pinfunction "2_2") (pintype "unspecified"))
      (node (ref "U5") (pin "4") (pinfunction "4_4") (pintype "unspecified"))
      (node (ref "U5") (pin "5") (pinfunction "5_5") (pintype "unspecified"))
      (node (ref "U9") (pin "2") (pinfunction "GND_2") (pintype "unspecified"))
      (node (ref "USB1") (pin "1") (pinfunction "GND_1") (pintype "unspecified"))
      (node (ref "USB1") (pin "12") (pinfunction "GND_12") (pintype "unspecified"))
      (node (ref "X1") (pin "2") (pinfunction "GND_2") (pintype "input"))
    )
    (net (code "14") (name "I2C_SCL") (class "Default")
      (node (ref "R20") (pin "1") (pinfunction "1_1") (pintype "input"))
      (node (ref "SCL1") (pin "1") (pinfunction "pad_1") (pintype "unspecified"))
      (node (ref "U2") (pin "28") (pinfunction "PB10_28") (pintype "unspecified"))
    )
    (net (code "15") (name "I2C_SDA") (class "Default")
      (node (ref "R21") (pin "1") (pinfunction "1_1") (pintype "input"))
      (node (ref "SDA1") (pin "1") (pinfunction "pad_1") (pintype "unspecified"))
      (node (ref "U2") (pin "29") (pinfunction "PB11_29") (pintype "unspecified"))
    )
    (net (code "16") (name "INT_GYRO") (class "Default")
      (node (ref "R2") (pin "12") (pinfunction "INT_12") (pintype "unspecified"))
      (node (ref "U2") (pin "25") (pinfunction "PB0_25") (pintype "unspecified"))
    )
    (net (code "17") (name "LED0") (class "Default")
      (node (ref "LED1") (pin "1") (pinfunction "A_1") (pintype "input"))
      (node (ref "U2") (pin "46") (pinfunction "PA13_46") (pintype "unspecified"))
    )
    (net (code "18") (name "MOTOR1") (class "Default")
      (node (ref "M1") (pin "1") (pinfunction "pad_1") (pintype "unspecified"))
      (node (ref "P1") (pin "6") (pinfunction "6_6") (pintype "unspecified"))
      (node (ref "U2") (pin "56") (pinfunction "PB4_56") (pintype "unspecified"))
    )
    (net (code "19") (name "MOTOR2") (class "Default")
      (node (ref "M2") (pin "1") (pinfunction "pad_1") (pintype "unspecified"))
      (node (ref "P1") (pin "5") (pinfunction "5_5") (pintype "unspecified"))
      (node (ref "U2") (pin "55") (pinfunction "PB3_55") (pintype "unspecified"))
    )
    (net (code "20") (name "MOTOR3") (class "Default")
      (node (ref "M3") (pin "1") (pinfunction "pad_1") (pintype "unspecified"))
      (node (ref "P1") (pin "4") (pinfunction "4_4") (pintype "unspecified"))
      (node (ref "U2") (pin "38") (pinfunction "PC7_38") (pintype "unspecified"))
    )
    (net (code "21") (name "MOTOR4") (class "Default")
      (node (ref "M4") (pin "1") (pinfunction "pad_1") (pintype "unspecified"))
      (node (ref "P1") (pin "3") (pinfunction "3_3") (pintype "unspecified"))
      (node (ref "U2") (pin "37") (pinfunction "PC6_37") (pintype "unspecified"))
    )
    (net (code "22") (name "Net-(C13-Pad2)") (class "Default")
      (node (ref "C13") (pin "2") (pinfunction "2_2") (pintype "input"))
      (node (ref "R22") (pin "2") (pinfunction "2_2") (pintype "input"))
    )
    (net (code "23") (name "Net-(C18-Pad2)") (class "Default")
      (node (ref "C18") (pin "2") (pinfunction "2_2") (pintype "input"))
      (node (ref "R12") (pin "2") (pinfunction "2_2") (pintype "input"))
    )
    (net (code "24") (name "Net-(D1-I{slash}O1-Pad6)") (class "Default")
      (node (ref "D1") (pin "6") (pinfunction "I/O1_6") (pintype "input"))
      (node (ref "R8") (pin "1") (pinfunction "1_1") (pintype "input"))
    )
    (net (code "25") (name "Net-(D1-I{slash}O2-Pad4)") (class "Default")
      (node (ref "D1") (pin "4") (pinfunction "I/O2_4") (pintype "input"))
      (node (ref "R9") (pin "1") (pinfunction "1_1") (pintype "input"))
    )
    (net (code "26") (name "Net-(LED1-C)") (class "Default")
      (node (ref "LED1") (pin "2") (pinfunction "C_2") (pintype "input"))
      (node (ref "R16") (pin "2") (pinfunction "2_2") (pintype "input"))
    )
    (net (code "27") (name "Net-(LED2-C)") (class "Default")
      (node (ref "LED2") (pin "1") (pinfunction "C_1") (pintype "input"))
      (node (ref "R14") (pin "2") (pinfunction "2_2") (pintype "input"))
    )
    (net (code "28") (name "Net-(LED3-C)") (class "Default")
      (node (ref "LED3") (pin "1") (pinfunction "C_1") (pintype "input"))
      (node (ref "R17") (pin "2") (pinfunction "2_2") (pintype "input"))
    )
    (net (code "29") (name "Net-(LED4-C)") (class "Default")
      (node (ref "LED4") (pin "1") (pinfunction "C_1") (pintype "input"))
      (node (ref "R1") (pin "2") (pinfunction "2_2") (pintype "input"))
    )
    (net (code "30") (name "Net-(R2-REGOUT)") (class "Default")
      (node (ref "C2") (pin "2") (pinfunction "2_2") (pintype "input"))
      (node (ref "R2") (pin "10") (pinfunction "REGOUT_10") (pintype "unspecified"))
    )
    (net (code "31") (name "Net-(R10-Pad2)") (class "Default")
      (node (ref "R10") (pin "2") (pinfunction "2_2") (pintype "input"))
      (node (ref "R26") (pin "1") (pinfunction "1_1") (pintype "unspecified"))
      (node (ref "R7") (pin "1") (pinfunction "1_1") (pintype "unspecified"))
    )
    (net (code "32") (name "Net-(R24-Pad2)") (class "Default")
      (node (ref "R24") (pin "2") (pinfunction "2_2") (pintype "input"))
      (node (ref "R29") (pin "1") (pinfunction "1_1") (pintype "unspecified"))
      (node (ref "R30") (pin "2") (pinfunction "2_2") (pintype "input"))
    )
    (net (code "33") (name "Net-(U1-BST)") (class "Default")
      (node (ref "R12") (pin "1") (pinfunction "1_1") (pintype "input"))
      (node (ref "U1") (pin "4") (pinfunction "BST_4") (pintype "unspecified"))
    )
    (net (code "34") (name "Net-(U1-EN{slash}SYNC)") (class "Default")
      (node (ref "R28") (pin "1") (pinfunction "1_1") (pintype "input"))
      (node (ref "U1") (pin "3") (pinfunction "EN/SYNC_3") (pintype "unspecified"))
    )
    (net (code "35") (name "Net-(U1-FB)") (class "Default")
      (node (ref "R10") (pin "1") (pinfunction "1_1") (pintype "input"))
      (node (ref "U1") (pin "1") (pinfunction "FB_1") (pintype "unspecified"))
    )
    (net (code "36") (name "Net-(U1-PG)") (class "Default")
      (node (ref "R27") (pin "2") (pinfunction "2_2") (pintype "input"))
      (node (ref "U1") (pin "8") (pinfunction "PG_8") (pintype "unspecified"))
    )
    (net (code "37") (name "Net-(U1-SW)") (class "Default")
      (node (ref "C18") (pin "1") (pinfunction "1_1") (pintype "input"))
      (node (ref "L2") (pin "1") (pinfunction "1_1") (pintype "unspecified"))
      (node (ref "U1") (pin "6") (pinfunction "SW_6") (pintype "unspecified"))
    )
    (net (code "38") (name "Net-(U1-VCC)") (class "Default")
      (node (ref "C21") (pin "2") (pinfunction "2_2") (pintype "input"))
      (node (ref "R27") (pin "1") (pinfunction "1_1") (pintype "input"))
      (node (ref "U1") (pin "2") (pinfunction "VCC_2") (pintype "unspecified"))
    )
    (net (code "39") (name "Net-(U2-PH0-OSC_IN)") (class "Default")
      (node (ref "U2") (pin "5") (pinfunction "PH0-OSC_IN_5") (pintype "unspecified"))
      (node (ref "X1") (pin "3") (pinfunction "OSC2_3") (pintype "input"))
    )
    (net (code "40") (name "Net-(U2-PH1-OSC_OUT)") (class "Default")
      (node (ref "U2") (pin "6") (pinfunction "PH1-OSC_OUT_6") (pintype "unspecified"))
      (node (ref "X1") (pin "1") (pinfunction "OSC1_1") (pintype "input"))
    )
    (net (code "41") (name "Net-(U2-VCAP_1)") (class "Default")
      (node (ref "C20") (pin "2") (pinfunction "2_2") (pintype "input"))
      (node (ref "U2") (pin "30") (pinfunction "VCAP_1_30") (pintype "unspecified"))
    )
    (net (code "42") (name "Net-(U3-BST)") (class "Default")
      (node (ref "R22") (pin "1") (pinfunction "1_1") (pintype "input"))
      (node (ref "U3") (pin "4") (pinfunction "BST_4") (pintype "unspecified"))
    )
    (net (code "43") (name "Net-(U3-EN{slash}SYNC)") (class "Default")
      (node (ref "R3") (pin "1") (pinfunction "1_1") (pintype "input"))
      (node (ref "U3") (pin "3") (pinfunction "EN/SYNC_3") (pintype "unspecified"))
    )
    (net (code "44") (name "Net-(U3-FB)") (class "Default")
      (node (ref "R24") (pin "1") (pinfunction "1_1") (pintype "input"))
      (node (ref "U3") (pin "1") (pinfunction "FB_1") (pintype "unspecified"))
    )
    (net (code "45") (name "Net-(U3-PG)") (class "Default")
      (node (ref "R4") (pin "2") (pinfunction "2_2") (pintype "input"))
      (node (ref "U3") (pin "8") (pinfunction "PG_8") (pintype "unspecified"))
    )
    (net (code "46") (name "Net-(U3-SW)") (class "Default")
      (node (ref "C13") (pin "1") (pinfunction "1_1") (pintype "input"))
      (node (ref "L1") (pin "1") (pinfunction "1_1") (pintype "unspecified"))
      (node (ref "U3") (pin "6") (pinfunction "SW_6") (pintype "unspecified"))
    )
    (net (code "47") (name "Net-(U3-VCC)") (class "Default")
      (node (ref "C9") (pin "2") (pinfunction "2_2") (pintype "input"))
      (node (ref "R4") (pin "1") (pinfunction "1_1") (pintype "input"))
      (node (ref "U3") (pin "2") (pinfunction "VCC_2") (pintype "unspecified"))
    )
    (net (code "48") (name "Net-(U4-IO2)") (class "Default")
      (node (ref "R5") (pin "1") (pinfunction "1_1") (pintype "input"))
      (node (ref "U4") (pin "3") (pinfunction "IO2_3") (pintype "unspecified"))
    )
    (net (code "49") (name "Net-(U4-IO3)") (class "Default")
      (node (ref "R6") (pin "1") (pinfunction "1_1") (pintype "input"))
      (node (ref "U4") (pin "7") (pinfunction "IO3_7") (pintype "unspecified"))
    )
    (net (code "50") (name "Net-(USB1-CC1)") (class "Default")
      (node (ref "R13") (pin "2") (pinfunction "2_2") (pintype "input"))
      (node (ref "USB1") (pin "4") (pinfunction "CC1_4") (pintype "unspecified"))
    )
    (net (code "51") (name "Net-(USB1-CC2)") (class "Default")
      (node (ref "R19") (pin "1") (pinfunction "1_1") (pintype "input"))
      (node (ref "USB1") (pin "10") (pinfunction "CC2_10") (pintype "unspecified"))
    )
    (net (code "52") (name "PIN_B-") (class "Default")
      (node (ref "B-1") (pin "1") (pinfunction "pad_1") (pintype "unspecified"))
      (node (ref "Q3") (pin "2") (pinfunction "S_2") (pintype "unspecified"))
    )
    (net (code "53") (name "SPI1_SCK") (class "Default")
      (node (ref "R2") (pin "23") (pinfunction "SCL/SCLK_23") (pintype "unspecified"))
      (node (ref "U2") (pin "21") (pinfunction "PA5_21") (pintype "unspecified"))
    )
    (net (code "54") (name "SPI1_SDI") (class "Default")
      (node (ref "R2") (pin "24") (pinfunction "SDA/SDI_24") (pintype "unspecified"))
      (node (ref "U2") (pin "23") (pinfunction "PA7_23") (pintype "unspecified"))
    )
    (net (code "55") (name "SPI1_SDO") (class "Default")
      (node (ref "R2") (pin "9") (pinfunction "AD0/SDO_9") (pintype "unspecified"))
      (node (ref "U2") (pin "22") (pinfunction "PA6_22") (pintype "unspecified"))
    )
    (net (code "56") (name "SPI2_SCK") (class "Default")
      (node (ref "U2") (pin "34") (pinfunction "PB13_34") (pintype "unspecified"))
      (node (ref "U4") (pin "6") (pinfunction "CLK_6") (pintype "unspecified"))
    )
    (net (code "57") (name "SPI2_SDI") (class "Default")
      (node (ref "U2") (pin "36") (pinfunction "PB15_36") (pintype "unspecified"))
      (node (ref "U4") (pin "5") (pinfunction "DI_5") (pintype "unspecified"))
    )
    (net (code "58") (name "SPI2_SDO") (class "Default")
      (node (ref "U2") (pin "35") (pinfunction "PB14_35") (pintype "unspecified"))
      (node (ref "U4") (pin "2") (pinfunction "DO_2") (pintype "unspecified"))
    )
    (net (code "59") (name "UART1_RX") (class "Default")
      (node (ref "RX1") (pin "1") (pinfunction "pad_1") (pintype "unspecified"))
      (node (ref "U10") (pin "1") (pinfunction "1_1") (pintype "unspecified"))
      (node (ref "U2") (pin "59") (pinfunction "PB7_59") (pintype "unspecified"))
    )
    (net (code "60") (name "UART1_TX") (class "Default")
      (node (ref "TX1") (pin "1") (pinfunction "pad_1") (pintype "unspecified"))
      (node (ref "U2") (pin "58") (pinfunction "PB6_58") (pintype "unspecified"))
    )
    (net (code "61") (name "UART2_RX") (class "Default")
      (node (ref "RX2") (pin "1") (pinfunction "pad_1") (pintype "unspecified"))
      (node (ref "U10") (pin "3") (pinfunction "3_3") (pintype "unspecified"))
      (node (ref "U2") (pin "17") (pinfunction "PA3_17") (pintype "unspecified"))
    )
    (net (code "62") (name "UART2_TX") (class "Default")
      (node (ref "CN1") (pin "2") (pinfunction "2_2") (pintype "unspecified"))
      (node (ref "TX2") (pin "1") (pinfunction "pad_1") (pintype "unspecified"))
      (node (ref "TX2A") (pin "1") (pinfunction "pad_1") (pintype "unspecified"))
      (node (ref "U10") (pin "4") (pinfunction "4_4") (pintype "unspecified"))
      (node (ref "U2") (pin "16") (pinfunction "PA2_16") (pintype "unspecified"))
    )
    (net (code "63") (name "UART3_RX") (class "Default")
      (node (ref "P1") (pin "2") (pinfunction "2_2") (pintype "unspecified"))
      (node (ref "RX5") (pin "1") (pinfunction "pad_1") (pintype "unspecified"))
      (node (ref "U2") (pin "52") (pinfunction "PC11_52") (pintype "unspecified"))
    )
    (net (code "64") (name "UART3_TX") (class "Default")
      (node (ref "TX5") (pin "1") (pinfunction "pad_1") (pintype "unspecified"))
      (node (ref "U2") (pin "51") (pinfunction "PC10_51") (pintype "unspecified"))
    )
    (net (code "65") (name "UART4_RX") (class "Default")
      (node (ref "RX6") (pin "1") (pinfunction "pad_1") (pintype "unspecified"))
      (node (ref "U2") (pin "15") (pinfunction "PA1_15") (pintype "unspecified"))
    )
    (net (code "66") (name "UART4_TX") (class "Default")
      (node (ref "TX6") (pin "1") (pinfunction "pad_1") (pintype "unspecified"))
      (node (ref "U2") (pin "14") (pinfunction "PA0-WKUP_14") (pintype "unspecified"))
    )
    (net (code "67") (name "UART5_RX") (class "Default")
      (node (ref "RX3") (pin "1") (pinfunction "pad_1") (pintype "unspecified"))
      (node (ref "U2") (pin "43") (pinfunction "PA10_43") (pintype "unspecified"))
    )
    (net (code "68") (name "UART5_TX") (class "Default")
      (node (ref "TX3") (pin "1") (pinfunction "pad_1") (pintype "unspecified"))
      (node (ref "U2") (pin "42") (pinfunction "PA9_42") (pintype "unspecified"))
    )
    (net (code "69") (name "USB_CON_D+") (class "Default")
      (node (ref "D1") (pin "3") (pinfunction "I/O2_3") (pintype "input"))
      (node (ref "USB1") (pin "6") (pinfunction "DP1_6") (pintype "unspecified"))
      (node (ref "USB1") (pin "8") (pinfunction "DP2_8") (pintype "unspecified"))
    )
    (net (code "70") (name "USB_CON_D-") (class "Default")
      (node (ref "D1") (pin "1") (pinfunction "I/O1_1") (pintype "input"))
      (node (ref "USB1") (pin "5") (pinfunction "DN2_5") (pintype "unspecified"))
      (node (ref "USB1") (pin "7") (pinfunction "DN1_7") (pintype "unspecified"))
    )
    (net (code "71") (name "USB_D+") (class "Default")
      (node (ref "R9") (pin "2") (pinfunction "2_2") (pintype "input"))
      (node (ref "U2") (pin "45") (pinfunction "PA12_45") (pintype "unspecified"))
    )
    (net (code "72") (name "USB_D-") (class "Default")
      (node (ref "R8") (pin "2") (pinfunction "2_2") (pintype "input"))
      (node (ref "U2") (pin "44") (pinfunction "PA11_44") (pintype "unspecified"))
    )
    (net (code "73") (name "VIDEO") (class "Default")
      (node (ref "CAM1") (pin "1") (pinfunction "pad_1") (pintype "unspecified"))
      (node (ref "CN1") (pin "1") (pinfunction "1_1") (pintype "unspecified"))
      (node (ref "U5") (pin "1") (pinfunction "1_1") (pintype "unspecified"))
      (node (ref "VTX1") (pin "1") (pinfunction "pad_1") (pintype "unspecified"))
    )
    (net (code "74") (name "unconnected-(R2-NC-Pad1)") (class "Default")
      (node (ref "R2") (pin "1") (pinfunction "NC_1") (pintype "unspecified+no_connect"))
    )
    (net (code "75") (name "unconnected-(R2-NC-Pad2)") (class "Default")
      (node (ref "R2") (pin "2") (pinfunction "NC_2") (pintype "unspecified+no_connect"))
    )
    (net (code "76") (name "unconnected-(R2-NC-Pad3)") (class "Default")
      (node (ref "R2") (pin "3") (pinfunction "NC_3") (pintype "unspecified+no_connect"))
    )
    (net (code "77") (name "unconnected-(R2-NC-Pad4)") (class "Default")
      (node (ref "R2") (pin "4") (pinfunction "NC_4") (pintype "unspecified+no_connect"))
    )
    (net (code "78") (name "unconnected-(R2-NC-Pad5)") (class "Default")
      (node (ref "R2") (pin "5") (pinfunction "NC_5") (pintype "unspecified+no_connect"))
    )
    (net (code "79") (name "unconnected-(R2-NC-Pad6)") (class "Default")
      (node (ref "R2") (pin "6") (pinfunction "NC_6") (pintype "unspecified+no_connect"))
    )
    (net (code "80") (name "unconnected-(R2-NC-Pad7)") (class "Default")
      (node (ref "R2") (pin "7") (pinfunction "NC_7") (pintype "unspecified+no_connect"))
    )
    (net (code "81") (name "unconnected-(R2-NC-Pad14)") (class "Default")
      (node (ref "R2") (pin "14") (pinfunction "NC_14") (pintype "unspecified+no_connect"))
    )
    (net (code "82") (name "unconnected-(R2-NC-Pad15)") (class "Default")
      (node (ref "R2") (pin "15") (pinfunction "NC_15") (pintype "unspecified+no_connect"))
    )
    (net (code "83") (name "unconnected-(R2-NC-Pad16)") (class "Default")
      (node (ref "R2") (pin "16") (pinfunction "NC_16") (pintype "unspecified+no_connect"))
    )
    (net (code "84") (name "unconnected-(R2-NC-Pad17)") (class "Default")
      (node (ref "R2") (pin "17") (pinfunction "NC_17") (pintype "unspecified+no_connect"))
    )
    (net (code "85") (name "unconnected-(R2-NC-Pad19)") (class "Default")
      (node (ref "R2") (pin "19") (pinfunction "NC_19") (pintype "unspecified+no_connect"))
    )
    (net (code "86") (name "unconnected-(R2-NC-Pad20)") (class "Default")
      (node (ref "R2") (pin "20") (pinfunction "NC_20") (pintype "unspecified+no_connect"))
    )
    (net (code "87") (name "unconnected-(R2-NC-Pad21)") (class "Default")
      (node (ref "R2") (pin "21") (pinfunction "NC_21") (pintype "unspecified+no_connect"))
    )
    (net (code "88") (name "unconnected-(U2-NRST-Pad7)") (class "Default")
      (node (ref "U2") (pin "7") (pinfunction "NRST_7") (pintype "unspecified+no_connect"))
    )
    (net (code "89") (name "unconnected-(U2-PA14-Pad49)") (class "Default")
      (node (ref "U2") (pin "49") (pinfunction "PA14_49") (pintype "unspecified+no_connect"))
    )
    (net (code "90") (name "unconnected-(U2-PA15-Pad50)") (class "Default")
      (node (ref "U2") (pin "50") (pinfunction "PA15_50") (pintype "unspecified+no_connect"))
    )
    (net (code "91") (name "unconnected-(U2-PB1-Pad26)") (class "Default")
      (node (ref "U2") (pin "26") (pinfunction "PB1_26") (pintype "unspecified+no_connect"))
    )
    (net (code "92") (name "unconnected-(U2-PB2-Pad27)") (class "Default")
      (node (ref "U2") (pin "27") (pinfunction "PB2_27") (pintype "unspecified+no_connect"))
    )
    (net (code "93") (name "unconnected-(U2-PB5-Pad57)") (class "Default")
      (node (ref "U2") (pin "57") (pinfunction "PB5_57") (pintype "unspecified+no_connect"))
    )
    (net (code "94") (name "unconnected-(U2-PB8-Pad61)") (class "Default")
      (node (ref "U2") (pin "61") (pinfunction "PB8_61") (pintype "unspecified+no_connect"))
    )
    (net (code "95") (name "unconnected-(U2-PB9-Pad62)") (class "Default")
      (node (ref "U2") (pin "62") (pinfunction "PB9_62") (pintype "unspecified+no_connect"))
    )
    (net (code "96") (name "unconnected-(U2-PB12-Pad33)") (class "Default")
      (node (ref "U2") (pin "33") (pinfunction "PB12_33") (pintype "unspecified+no_connect"))
    )
    (net (code "97") (name "unconnected-(U2-PC0-Pad8)") (class "Default")
      (node (ref "U2") (pin "8") (pinfunction "PC0_8") (pintype "unspecified+no_connect"))
    )
    (net (code "98") (name "unconnected-(U2-PC2-Pad10)") (class "Default")
      (node (ref "U2") (pin "10") (pinfunction "PC2_10") (pintype "unspecified+no_connect"))
    )
    (net (code "99") (name "unconnected-(U2-PC4-Pad24)") (class "Default")
      (node (ref "U2") (pin "24") (pinfunction "PC4_24") (pintype "unspecified+no_connect"))
    )
    (net (code "100") (name "unconnected-(U2-PC8-Pad39)") (class "Default")
      (node (ref "U2") (pin "39") (pinfunction "PC8_39") (pintype "unspecified+no_connect"))
    )
    (net (code "101") (name "unconnected-(U2-PC9-Pad40)") (class "Default")
      (node (ref "U2") (pin "40") (pinfunction "PC9_40") (pintype "unspecified+no_connect"))
    )
    (net (code "102") (name "unconnected-(U2-PC12-Pad53)") (class "Default")
      (node (ref "U2") (pin "53") (pinfunction "PC12_53") (pintype "unspecified+no_connect"))
    )
    (net (code "103") (name "unconnected-(U2-PC13-Pad2)") (class "Default")
      (node (ref "U2") (pin "2") (pinfunction "PC13_2") (pintype "unspecified+no_connect"))
    )
    (net (code "104") (name "unconnected-(U2-PC14-OSC32_IN-Pad3)") (class "Default")
      (node (ref "U2") (pin "3") (pinfunction "PC14-OSC32_IN_3") (pintype "unspecified+no_connect"))
    )
    (net (code "105") (name "unconnected-(U2-PD2-Pad54)") (class "Default")
      (node (ref "U2") (pin "54") (pinfunction "PD2_54") (pintype "unspecified+no_connect"))
    )
    (net (code "106") (name "unconnected-(U9-NC-Pad4)") (class "Default")
      (node (ref "U9") (pin "4") (pinfunction "NC_4") (pintype "unspecified+no_connect"))
    )
    (net (code "107") (name "unconnected-(USB1-SBU1-Pad9)") (class "Default")
      (node (ref "USB1") (pin "9") (pinfunction "SBU1_9") (pintype "unspecified+no_connect"))
    )
    (net (code "108") (name "unconnected-(USB1-SBU2-Pad3)") (class "Default")
      (node (ref "USB1") (pin "3") (pinfunction "SBU2_3") (pintype "unspecified+no_connect"))
    )
    (net (code "109") (name "unconnected-(USB1-SHELL-Pad13)") (class "Default")
      (node (ref "USB1") (pin "13") (pinfunction "SHELL_13") (pintype "unspecified+no_connect"))
    )
    (net (code "110") (name "unconnected-(USB1-SHELL-Pad14)") (class "Default")
      (node (ref "USB1") (pin "14") (pinfunction "SHELL_14") (pintype "unspecified+no_connect"))
    )
  )
)
